# hr20.net
KiCad netlist of a schematic drawn in EAGLE
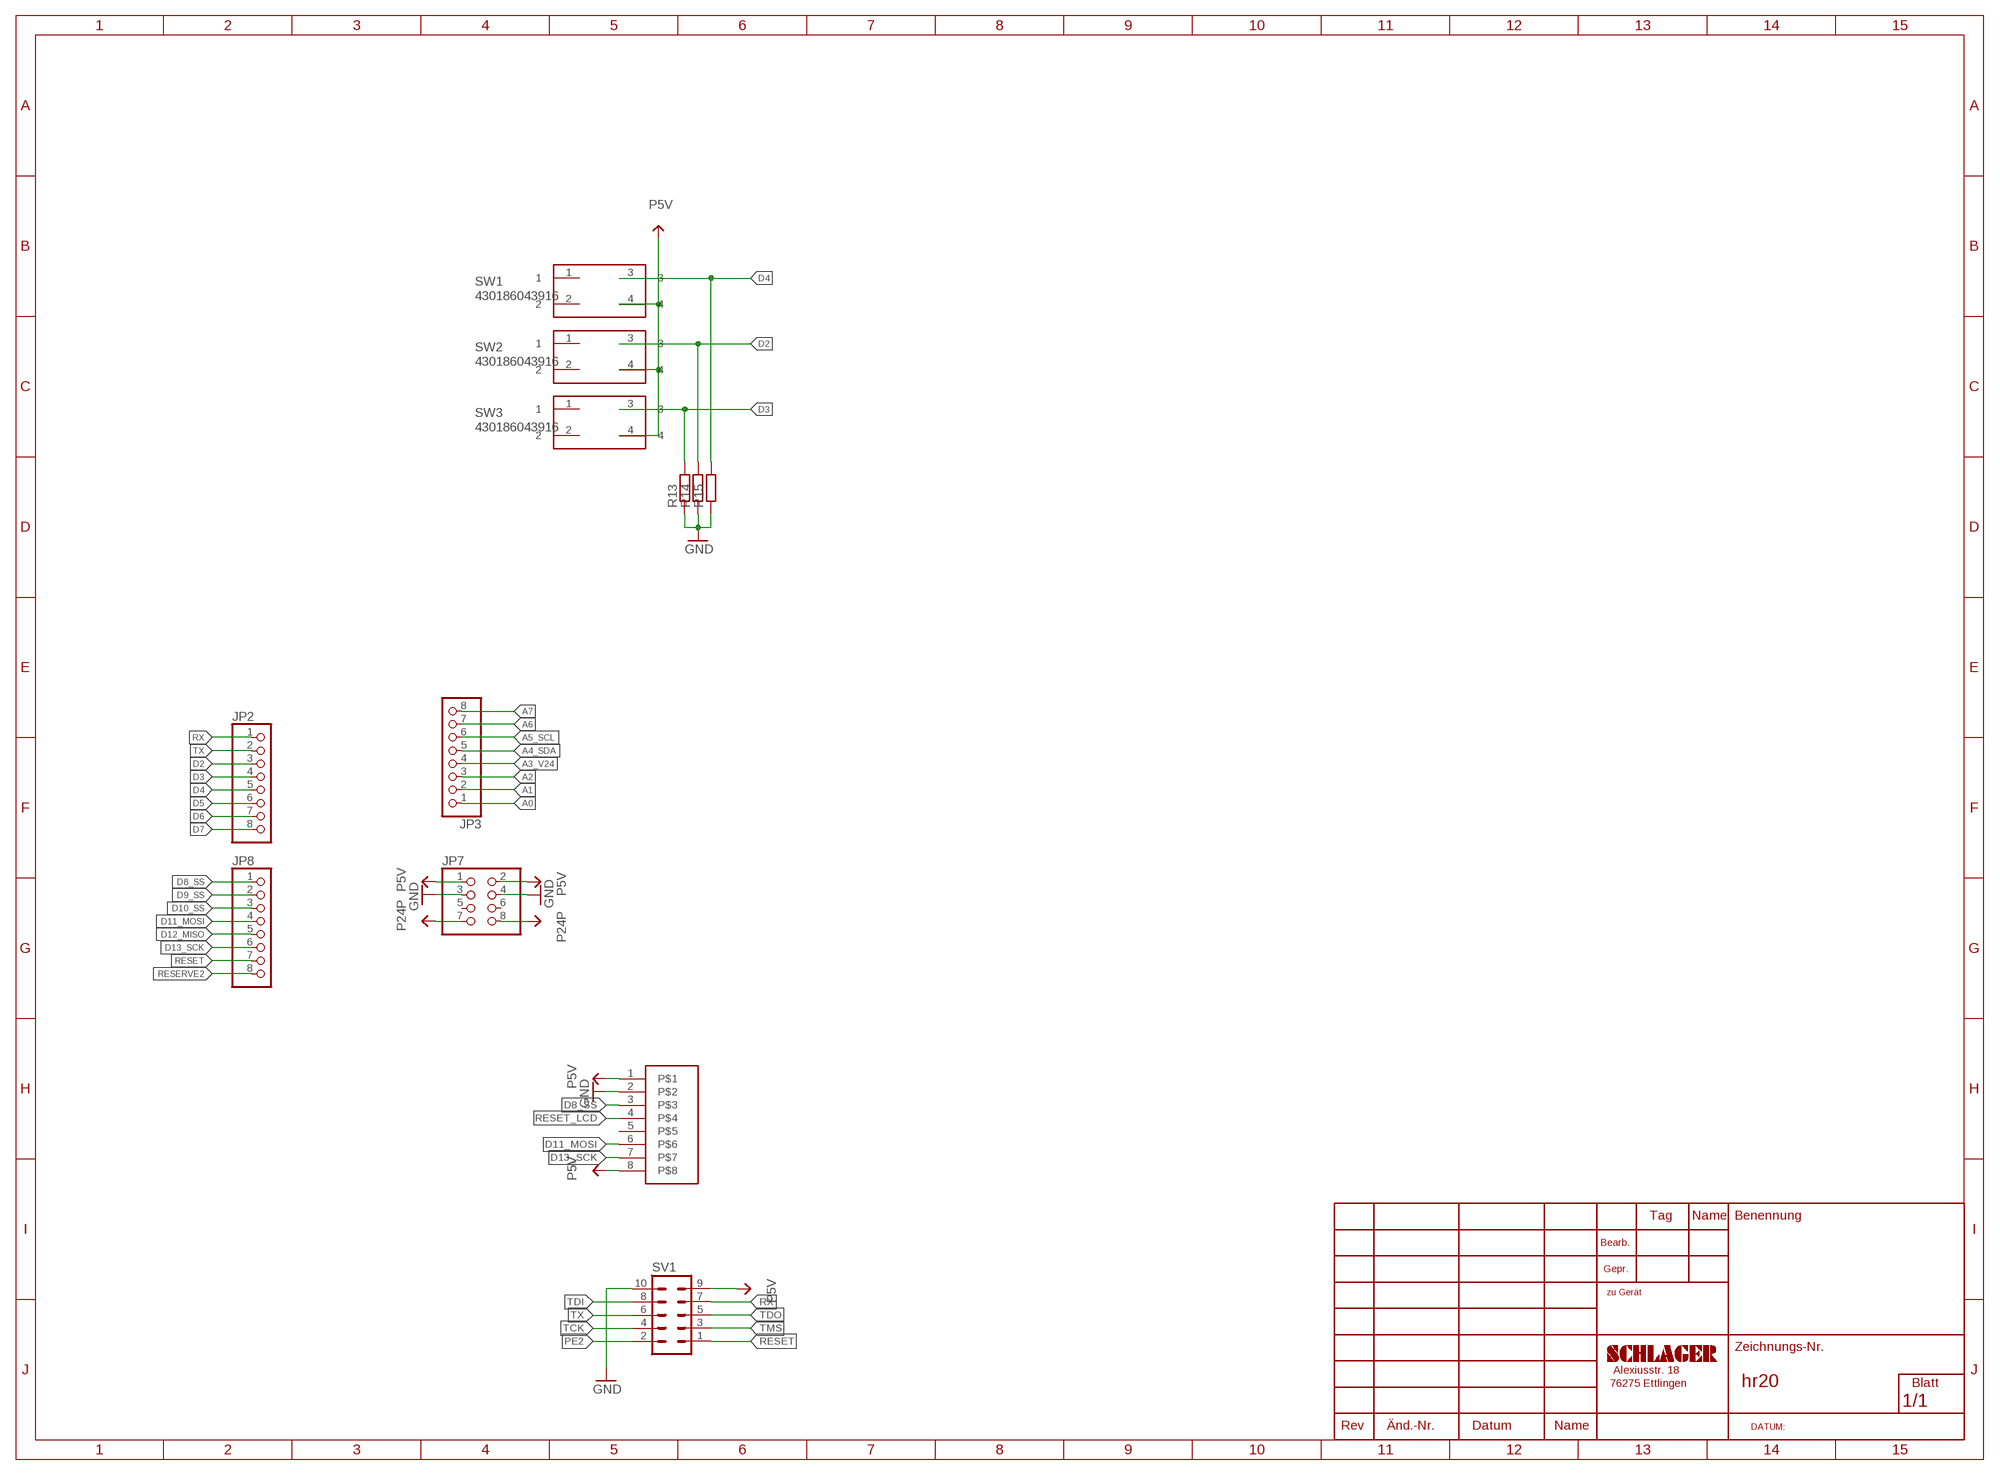
[diagram p0: schematic, sheet 1]

(export (version "E")
  (design (tool "Eeschema 10.0.6"))
  (components
    (comp (ref "JP2")
      (value "PINHD-1X8")
      (footprint "eagle-import:1X08")
      (libsource (lib "eagle-import") (part "PINHD-1X8"))
    )
    (comp (ref "JP3")
      (value "PINHD-1X8")
      (footprint "eagle-import:1X08")
      (libsource (lib "eagle-import") (part "PINHD-1X8"))
    )
    (comp (ref "JP7")
      (value "PINHD-2X4")
      (footprint "eagle-import:2X04")
      (libsource (lib "eagle-import") (part "PINHD-2X4"))
    )
    (comp (ref "JP8")
      (value "PINHD-1X8")
      (footprint "eagle-import:1X08")
      (libsource (lib "eagle-import") (part "PINHD-1X8"))
    )
    (comp (ref "R13")
      (value "R-EU_0207/10")
      (footprint "eagle-import:0207_10")
      (libsource (lib "eagle-import") (part "R-EU_0207/10"))
    )
    (comp (ref "R14")
      (value "R-EU_0207/10")
      (footprint "eagle-import:0207_10")
      (libsource (lib "eagle-import") (part "R-EU_0207/10"))
    )
    (comp (ref "R15")
      (value "R-EU_0207/10")
      (footprint "eagle-import:0207_10")
      (libsource (lib "eagle-import") (part "R-EU_0207/10"))
    )
    (comp (ref "SV1")
      (value "ML10")
      (footprint "eagle-import:ML10")
      (libsource (lib "eagle-import") (part "ML10"))
    )
    (comp (ref "SW1")
      (value "430186043916")
      (footprint "eagle-import:430186043916")
      (libsource (lib "eagle-import") (part "430186043916"))
    )
    (comp (ref "SW2")
      (value "430186043916")
      (footprint "eagle-import:430186043916")
      (libsource (lib "eagle-import") (part "430186043916"))
    )
    (comp (ref "SW3")
      (value "430186043916")
      (footprint "eagle-import:430186043916")
      (libsource (lib "eagle-import") (part "430186043916"))
    )
    (comp (ref "U$2")
      (value "1.44-128X128")
      (footprint "eagle-import:1.44-128X128")
      (libsource (lib "eagle-import") (part "1.44-128X128"))
    )
  )
  (nets
    (net (code "1") (name "A0") (class "Default")
      (node (ref "JP3") (pin "1") (pinfunction "1_1") (pintype "passive"))
    )
    (net (code "2") (name "A1") (class "Default")
      (node (ref "JP3") (pin "2") (pinfunction "2_2") (pintype "passive"))
    )
    (net (code "3") (name "A2") (class "Default")
      (node (ref "JP3") (pin "3") (pinfunction "3_3") (pintype "passive"))
    )
    (net (code "4") (name "A3_V24") (class "Default")
      (node (ref "JP3") (pin "4") (pinfunction "4_4") (pintype "passive"))
    )
    (net (code "5") (name "A4_SDA") (class "Default")
      (node (ref "JP3") (pin "5") (pinfunction "5_5") (pintype "passive"))
    )
    (net (code "6") (name "A5_SCL") (class "Default")
      (node (ref "JP3") (pin "6") (pinfunction "6_6") (pintype "passive"))
    )
    (net (code "7") (name "A6") (class "Default")
      (node (ref "JP3") (pin "7") (pinfunction "7_7") (pintype "passive"))
    )
    (net (code "8") (name "A7") (class "Default")
      (node (ref "JP3") (pin "8") (pinfunction "8_8") (pintype "passive"))
    )
    (net (code "9") (name "D2") (class "Default")
      (node (ref "JP2") (pin "3") (pinfunction "3_3") (pintype "passive"))
      (node (ref "R14") (pin "2") (pinfunction "2_2") (pintype "passive"))
      (node (ref "SW2") (pin "3") (pinfunction "3_3") (pintype "bidirectional"))
    )
    (net (code "10") (name "D3") (class "Default")
      (node (ref "JP2") (pin "4") (pinfunction "4_4") (pintype "passive"))
      (node (ref "R13") (pin "2") (pinfunction "2_2") (pintype "passive"))
      (node (ref "SW3") (pin "3") (pinfunction "3_3") (pintype "bidirectional"))
    )
    (net (code "11") (name "D4") (class "Default")
      (node (ref "JP2") (pin "5") (pinfunction "5_5") (pintype "passive"))
      (node (ref "R15") (pin "2") (pinfunction "2_2") (pintype "passive"))
      (node (ref "SW1") (pin "3") (pinfunction "3_3") (pintype "bidirectional"))
    )
    (net (code "12") (name "D5") (class "Default")
      (node (ref "JP2") (pin "6") (pinfunction "6_6") (pintype "passive"))
    )
    (net (code "13") (name "D6") (class "Default")
      (node (ref "JP2") (pin "7") (pinfunction "7_7") (pintype "passive"))
    )
    (net (code "14") (name "D7") (class "Default")
      (node (ref "JP2") (pin "8") (pinfunction "8_8") (pintype "passive"))
    )
    (net (code "15") (name "D8_SS") (class "Default")
      (node (ref "JP8") (pin "1") (pinfunction "1_1") (pintype "passive"))
      (node (ref "U$2") (pin "3") (pinfunction "P$3_3") (pintype "bidirectional"))
    )
    (net (code "16") (name "D9_SS") (class "Default")
      (node (ref "JP8") (pin "2") (pinfunction "2_2") (pintype "passive"))
    )
    (net (code "17") (name "D10_SS") (class "Default")
      (node (ref "JP8") (pin "3") (pinfunction "3_3") (pintype "passive"))
    )
    (net (code "18") (name "D11_MOSI") (class "Default")
      (node (ref "JP8") (pin "4") (pinfunction "4_4") (pintype "passive"))
      (node (ref "U$2") (pin "6") (pinfunction "P$6_6") (pintype "bidirectional"))
    )
    (net (code "19") (name "D12_MISO") (class "Default")
      (node (ref "JP8") (pin "5") (pinfunction "5_5") (pintype "passive"))
    )
    (net (code "20") (name "D13_SCK") (class "Default")
      (node (ref "JP8") (pin "6") (pinfunction "6_6") (pintype "passive"))
      (node (ref "U$2") (pin "7") (pinfunction "P$7_7") (pintype "bidirectional"))
    )
    (net (code "21") (name "GND") (class "Default")
      (node (ref "JP7") (pin "3") (pinfunction "3_3") (pintype "passive"))
      (node (ref "JP7") (pin "4") (pinfunction "4_4") (pintype "passive"))
      (node (ref "R13") (pin "1") (pinfunction "1_1") (pintype "passive"))
      (node (ref "R14") (pin "1") (pinfunction "1_1") (pintype "passive"))
      (node (ref "R15") (pin "1") (pinfunction "1_1") (pintype "passive"))
      (node (ref "SV1") (pin "10") (pinfunction "10_10") (pintype "passive"))
      (node (ref "U$2") (pin "2") (pinfunction "P$2_2") (pintype "bidirectional"))
    )
    (net (code "22") (name "P5V") (class "Default")
      (node (ref "JP7") (pin "1") (pinfunction "1_1") (pintype "passive"))
      (node (ref "JP7") (pin "2") (pinfunction "2_2") (pintype "passive"))
      (node (ref "SV1") (pin "9") (pinfunction "9_9") (pintype "passive"))
      (node (ref "SW1") (pin "4") (pinfunction "4_4") (pintype "bidirectional"))
      (node (ref "SW2") (pin "4") (pinfunction "4_4") (pintype "bidirectional"))
      (node (ref "SW3") (pin "4") (pinfunction "4_4") (pintype "bidirectional"))
      (node (ref "U$2") (pin "1") (pinfunction "P$1_1") (pintype "bidirectional"))
      (node (ref "U$2") (pin "8") (pinfunction "P$8_8") (pintype "bidirectional"))
    )
    (net (code "23") (name "P24P") (class "Default")
      (node (ref "JP7") (pin "7") (pinfunction "7_7") (pintype "passive"))
      (node (ref "JP7") (pin "8") (pinfunction "8_8") (pintype "passive"))
    )
    (net (code "24") (name "PE2") (class "Default")
      (node (ref "SV1") (pin "2") (pinfunction "2_2") (pintype "passive"))
    )
    (net (code "25") (name "RESERVE2") (class "Default")
      (node (ref "JP8") (pin "8") (pinfunction "8_8") (pintype "passive"))
    )
    (net (code "26") (name "RESET") (class "Default")
      (node (ref "JP8") (pin "7") (pinfunction "7_7") (pintype "passive"))
      (node (ref "SV1") (pin "1") (pinfunction "1_1") (pintype "passive"))
    )
    (net (code "27") (name "RESET_LCD") (class "Default")
      (node (ref "U$2") (pin "4") (pinfunction "P$4_4") (pintype "bidirectional"))
    )
    (net (code "28") (name "RX") (class "Default")
      (node (ref "JP2") (pin "1") (pinfunction "1_1") (pintype "passive"))
      (node (ref "SV1") (pin "7") (pinfunction "7_7") (pintype "passive"))
    )
    (net (code "29") (name "TCK") (class "Default")
      (node (ref "SV1") (pin "4") (pinfunction "4_4") (pintype "passive"))
    )
    (net (code "30") (name "TDI") (class "Default")
      (node (ref "SV1") (pin "8") (pinfunction "8_8") (pintype "passive"))
    )
    (net (code "31") (name "TDO") (class "Default")
      (node (ref "SV1") (pin "5") (pinfunction "5_5") (pintype "passive"))
    )
    (net (code "32") (name "TMS") (class "Default")
      (node (ref "SV1") (pin "3") (pinfunction "3_3") (pintype "passive"))
    )
    (net (code "33") (name "TX") (class "Default")
      (node (ref "JP2") (pin "2") (pinfunction "2_2") (pintype "passive"))
      (node (ref "SV1") (pin "6") (pinfunction "6_6") (pintype "passive"))
    )
    (net (code "34") (name "unconnected-(JP7-Pad5)") (class "Default")
      (node (ref "JP7") (pin "5") (pinfunction "5_5") (pintype "passive"))
    )
    (net (code "35") (name "unconnected-(JP7-Pad6)") (class "Default")
      (node (ref "JP7") (pin "6") (pinfunction "6_6") (pintype "passive"))
    )
    (net (code "36") (name "unconnected-(SW1-Pad1)") (class "Default")
      (node (ref "SW1") (pin "1") (pinfunction "1_1") (pintype "bidirectional"))
    )
    (net (code "37") (name "unconnected-(SW1-Pad2)") (class "Default")
      (node (ref "SW1") (pin "2") (pinfunction "2_2") (pintype "bidirectional"))
    )
    (net (code "38") (name "unconnected-(SW2-Pad1)") (class "Default")
      (node (ref "SW2") (pin "1") (pinfunction "1_1") (pintype "bidirectional"))
    )
    (net (code "39") (name "unconnected-(SW2-Pad2)") (class "Default")
      (node (ref "SW2") (pin "2") (pinfunction "2_2") (pintype "bidirectional"))
    )
    (net (code "40") (name "unconnected-(SW3-Pad1)") (class "Default")
      (node (ref "SW3") (pin "1") (pinfunction "1_1") (pintype "bidirectional"))
    )
    (net (code "41") (name "unconnected-(SW3-Pad2)") (class "Default")
      (node (ref "SW3") (pin "2") (pinfunction "2_2") (pintype "bidirectional"))
    )
    (net (code "42") (name "unconnected-(U$2-P$5-Pad5)") (class "Default")
      (node (ref "U$2") (pin "5") (pinfunction "P$5_5") (pintype "bidirectional"))
    )
  )
)
